# PCB_12V5A_60Wascii.net
KiCad netlist of a schematic drawn in Altium Designer
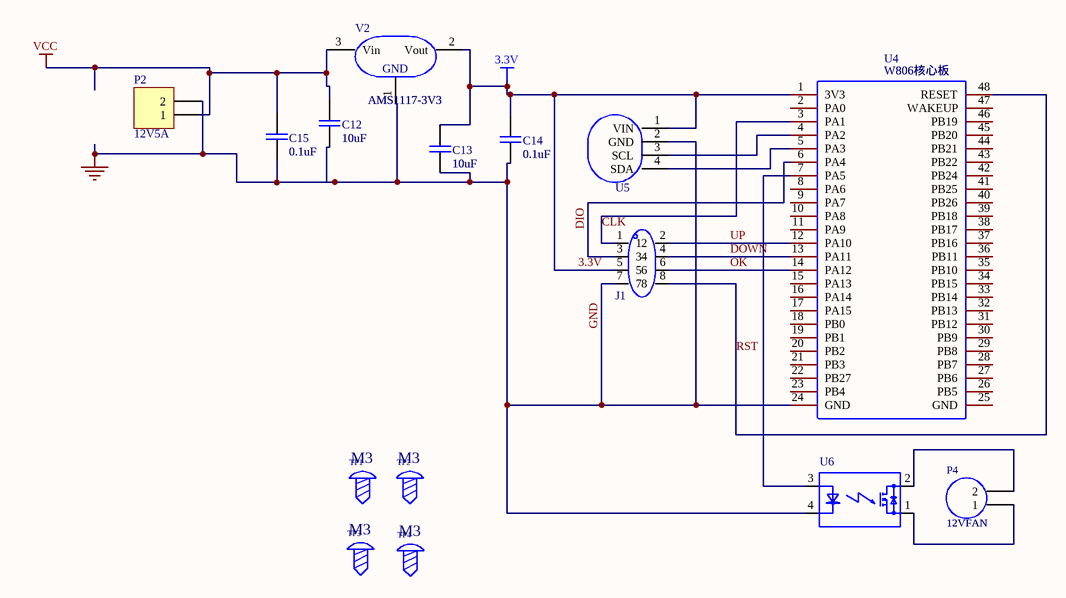
[diagram p0: PCB方案验证板  12V5A 60Wascii.SchDoc]

(export (version "E")
  (design (tool "Eeschema 10.0.6"))
  (components
    (comp (ref "C12")
      (value "10uF")
      (footprint "0805-C")
      (fields (field (name "NAME") "10uF"))
      (libsource (lib "altium-import") (part "root_1_CAP-SMT_"))
    )
    (comp (ref "C13")
      (value "10uF")
      (footprint "0805-C")
      (fields (field (name "NAME") "10uF"))
      (libsource (lib "altium-import") (part "root_1_CAP-SMT_"))
    )
    (comp (ref "C14")
      (value "0.1uF")
      (footprint "0805-C")
      (fields (field (name "NAME") "0.1uF"))
      (libsource (lib "altium-import") (part "root_1_CAP-SMT_"))
    )
    (comp (ref "C15")
      (value "0.1uF")
      (footprint "0805-C")
      (fields (field (name "NAME") "0.1uF"))
      (libsource (lib "") (part "root_1_CAP-SMT__1"))
    )
    (comp (ref "J1")
      (value "~")
      (footprint "HDR-TH_8P-P2.54-V-F-R2-C4-S2.54-1")
      (fields (field (name "MANUFACTURER PART") "2.54mm,24Doublerowfemale"))
      (libsource (lib "altium-import") (part "root_0_2.54mm,2×4Doublerowfemale_"))
    )
    (comp (ref "P2")
      (value "12V5A")
      (footprint "OUT")
      (description "Header, 2-Pin")
      (fields (field (name "PUBLISHER") "Altium Limited"))
      (libsource (lib "Miscellaneous Connectors") (part "Header 2"))
    )
    (comp (ref "P4")
      (value "12VFAN")
      (footprint "OUT")
      (fields (field (name "NAME") "12VFAN") (field (name "PUBLISHER") "Altium Limited"))
      (libsource (lib "altium-import") (part "root_2_12V5A_"))
    )
    (comp (ref "TP1")
      (value "~")
      (footprint "M3x8+6_N")
      (libsource (lib "altium-import") (part "root_0_M3_"))
    )
    (comp (ref "TP2")
      (value "~")
      (footprint "M3x8+6_N")
      (libsource (lib "altium-import") (part "root_0_M3_"))
    )
    (comp (ref "TP3")
      (value "~")
      (footprint "M3x8+6_N")
      (libsource (lib "altium-import") (part "root_0_M3_"))
    )
    (comp (ref "TP4")
      (value "~")
      (footprint "M3x8+6_N")
      (libsource (lib "altium-import") (part "root_0_M3_"))
    )
    (comp (ref "U4")
      (value "W806核心板")
      (footprint "w806")
      (fields (field (name "NAME") "W806核心板"))
      (libsource (lib "altium-import") (part "root_0_W806核心板_"))
    )
    (comp (ref "U5")
      (value "~")
      (footprint "AHT10")
      (libsource (lib "altium-import") (part "root_0_AHT10温湿度传感器_"))
    )
    (comp (ref "U6")
      (value "~")
      (footprint "w806:RELAY-TH_4P-L43.5-W10.3-PMN")
      (fields (field (name "MANUFACTURER") "PANASONIC(松下)") (field (name "MANUFACTURER PART") "AQZ102D"))
      (libsource (lib "altium-import") (part "root_0_PMN5D6132_ENMG_"))
    )
    (comp (ref "V2")
      (value "AMS1117-3V3")
      (footprint "PG-SOT223-4_L6.5-W3.5-P2.30-LS7.0-BR")
      (fields (field (name "NAME") "AMS1117-3V3"))
      (libsource (lib "altium-import") (part "root_0_AMS1117_"))
    )
  )
  (nets
    (net (code "1") (name "/CLK") (class "Default")
      (node (ref "J1") (pin "1") (pinfunction "1_1") (pintype "passive"))
      (node (ref "U4") (pin "3") (pinfunction "PA1_3") (pintype "passive"))
    )
    (net (code "2") (name "/DIO") (class "Default")
      (node (ref "J1") (pin "3") (pinfunction "3_3") (pintype "passive"))
      (node (ref "U4") (pin "6") (pinfunction "PA4_6") (pintype "passive"))
    )
    (net (code "3") (name "/DOWN") (class "Default")
      (node (ref "J1") (pin "4") (pinfunction "4_4") (pintype "passive"))
      (node (ref "U4") (pin "13") (pinfunction "PA11_13") (pintype "passive"))
    )
    (net (code "4") (name "/OK") (class "Default")
      (node (ref "J1") (pin "6") (pinfunction "6_6") (pintype "passive"))
      (node (ref "U4") (pin "14") (pinfunction "PA12_14") (pintype "passive"))
    )
    (net (code "5") (name "/RST") (class "Default")
      (node (ref "J1") (pin "8") (pinfunction "8_8") (pintype "passive"))
      (node (ref "U4") (pin "48") (pinfunction "RESET_48") (pintype "passive"))
    )
    (net (code "6") (name "/UP") (class "Default")
      (node (ref "J1") (pin "2") (pinfunction "2_2") (pintype "passive"))
      (node (ref "U4") (pin "12") (pinfunction "PA10_12") (pintype "passive"))
    )
    (net (code "7") (name "3.3V") (class "Default")
      (node (ref "C13") (pin "2") (pinfunction "2_2") (pintype "passive"))
      (node (ref "C14") (pin "2") (pinfunction "2_2") (pintype "passive"))
      (node (ref "J1") (pin "5") (pinfunction "5_5") (pintype "passive"))
      (node (ref "U4") (pin "1") (pinfunction "3V3_1") (pintype "passive"))
      (node (ref "U5") (pin "1") (pinfunction "VIN_1") (pintype "passive"))
      (node (ref "V2") (pin "2") (pinfunction "Vout_2") (pintype "passive"))
    )
    (net (code "8") (name "GND") (class "Default")
      (node (ref "C12") (pin "1") (pinfunction "1_1") (pintype "passive"))
      (node (ref "C13") (pin "1") (pinfunction "1_1") (pintype "passive"))
      (node (ref "C14") (pin "1") (pinfunction "1_1") (pintype "passive"))
      (node (ref "C15") (pin "1") (pinfunction "1_1") (pintype "passive"))
      (node (ref "J1") (pin "7") (pinfunction "7_7") (pintype "passive"))
      (node (ref "P2") (pin "GND") (pinfunction "2_GND") (pintype "passive"))
      (node (ref "U4") (pin "24") (pinfunction "GND_24") (pintype "passive"))
      (node (ref "U5") (pin "2") (pinfunction "GND_2") (pintype "passive"))
      (node (ref "U6") (pin "4") (pinfunction "+_4") (pintype "passive"))
      (node (ref "V2") (pin "1") (pinfunction "GND_1") (pintype "passive"))
    )
    (net (code "9") (name "Net-(P4-1)") (class "Default")
      (node (ref "P4") (pin "VCC") (pinfunction "1_VCC") (pintype "passive"))
      (node (ref "U6") (pin "1") (pinfunction "K_1") (pintype "passive"))
    )
    (net (code "10") (name "Net-(P4-2)") (class "Default")
      (node (ref "P4") (pin "GND") (pinfunction "2_GND") (pintype "passive"))
      (node (ref "U6") (pin "2") (pinfunction "A_2") (pintype "passive"))
    )
    (net (code "11") (name "Net-(U4-PA2)") (class "Default")
      (node (ref "U4") (pin "4") (pinfunction "PA2_4") (pintype "passive"))
      (node (ref "U5") (pin "3") (pinfunction "SCL_3") (pintype "passive"))
    )
    (net (code "12") (name "Net-(U4-PA3)") (class "Default")
      (node (ref "U4") (pin "5") (pinfunction "PA3_5") (pintype "passive"))
      (node (ref "U5") (pin "4") (pinfunction "SDA_4") (pintype "passive"))
    )
    (net (code "13") (name "Net-(U4-PA5)") (class "Default")
      (node (ref "U4") (pin "7") (pinfunction "PA5_7") (pintype "passive"))
      (node (ref "U6") (pin "3") (pinfunction "-_3") (pintype "passive"))
    )
    (net (code "14") (name "VCC") (class "Default")
      (node (ref "C12") (pin "2") (pinfunction "2_2") (pintype "passive"))
      (node (ref "C15") (pin "2") (pinfunction "2_2") (pintype "passive"))
      (node (ref "P2") (pin "VCC") (pinfunction "1_VCC") (pintype "passive"))
      (node (ref "V2") (pin "3") (pinfunction "Vin_3") (pintype "passive"))
    )
    (net (code "15") (name "unconnected-(U4-GND-Pad25)") (class "Default")
      (node (ref "U4") (pin "25") (pinfunction "GND_25") (pintype "passive"))
    )
    (net (code "16") (name "unconnected-(U4-PA0-Pad2)") (class "Default")
      (node (ref "U4") (pin "2") (pinfunction "PA0_2") (pintype "passive"))
    )
    (net (code "17") (name "unconnected-(U4-PA6-Pad8)") (class "Default")
      (node (ref "U4") (pin "8") (pinfunction "PA6_8") (pintype "passive"))
    )
    (net (code "18") (name "unconnected-(U4-PA7-Pad9)") (class "Default")
      (node (ref "U4") (pin "9") (pinfunction "PA7_9") (pintype "passive"))
    )
    (net (code "19") (name "unconnected-(U4-PA8-Pad10)") (class "Default")
      (node (ref "U4") (pin "10") (pinfunction "PA8_10") (pintype "passive"))
    )
    (net (code "20") (name "unconnected-(U4-PA9-Pad11)") (class "Default")
      (node (ref "U4") (pin "11") (pinfunction "PA9_11") (pintype "passive"))
    )
    (net (code "21") (name "unconnected-(U4-PA13-Pad15)") (class "Default")
      (node (ref "U4") (pin "15") (pinfunction "PA13_15") (pintype "passive"))
    )
    (net (code "22") (name "unconnected-(U4-PA14-Pad16)") (class "Default")
      (node (ref "U4") (pin "16") (pinfunction "PA14_16") (pintype "passive"))
    )
    (net (code "23") (name "unconnected-(U4-PA15-Pad17)") (class "Default")
      (node (ref "U4") (pin "17") (pinfunction "PA15_17") (pintype "passive"))
    )
    (net (code "24") (name "unconnected-(U4-PB0-Pad18)") (class "Default")
      (node (ref "U4") (pin "18") (pinfunction "PB0_18") (pintype "passive"))
    )
    (net (code "25") (name "unconnected-(U4-PB1-Pad19)") (class "Default")
      (node (ref "U4") (pin "19") (pinfunction "PB1_19") (pintype "passive"))
    )
    (net (code "26") (name "unconnected-(U4-PB2-Pad20)") (class "Default")
      (node (ref "U4") (pin "20") (pinfunction "PB2_20") (pintype "passive"))
    )
    (net (code "27") (name "unconnected-(U4-PB3-Pad21)") (class "Default")
      (node (ref "U4") (pin "21") (pinfunction "PB3_21") (pintype "passive"))
    )
    (net (code "28") (name "unconnected-(U4-PB4-Pad23)") (class "Default")
      (node (ref "U4") (pin "23") (pinfunction "PB4_23") (pintype "passive"))
    )
    (net (code "29") (name "unconnected-(U4-PB5-Pad26)") (class "Default")
      (node (ref "U4") (pin "26") (pinfunction "PB5_26") (pintype "passive"))
    )
    (net (code "30") (name "unconnected-(U4-PB6-Pad27)") (class "Default")
      (node (ref "U4") (pin "27") (pinfunction "PB6_27") (pintype "passive"))
    )
    (net (code "31") (name "unconnected-(U4-PB7-Pad28)") (class "Default")
      (node (ref "U4") (pin "28") (pinfunction "PB7_28") (pintype "passive"))
    )
    (net (code "32") (name "unconnected-(U4-PB8-Pad29)") (class "Default")
      (node (ref "U4") (pin "29") (pinfunction "PB8_29") (pintype "passive"))
    )
    (net (code "33") (name "unconnected-(U4-PB9-Pad30)") (class "Default")
      (node (ref "U4") (pin "30") (pinfunction "PB9_30") (pintype "passive"))
    )
    (net (code "34") (name "unconnected-(U4-PB10-Pad35)") (class "Default")
      (node (ref "U4") (pin "35") (pinfunction "PB10_35") (pintype "passive"))
    )
    (net (code "35") (name "unconnected-(U4-PB11-Pad36)") (class "Default")
      (node (ref "U4") (pin "36") (pinfunction "PB11_36") (pintype "passive"))
    )
    (net (code "36") (name "unconnected-(U4-PB12-Pad31)") (class "Default")
      (node (ref "U4") (pin "31") (pinfunction "PB12_31") (pintype "passive"))
    )
    (net (code "37") (name "unconnected-(U4-PB13-Pad32)") (class "Default")
      (node (ref "U4") (pin "32") (pinfunction "PB13_32") (pintype "passive"))
    )
    (net (code "38") (name "unconnected-(U4-PB14-Pad33)") (class "Default")
      (node (ref "U4") (pin "33") (pinfunction "PB14_33") (pintype "passive"))
    )
    (net (code "39") (name "unconnected-(U4-PB15-Pad34)") (class "Default")
      (node (ref "U4") (pin "34") (pinfunction "PB15_34") (pintype "passive"))
    )
    (net (code "40") (name "unconnected-(U4-PB16-Pad37)") (class "Default")
      (node (ref "U4") (pin "37") (pinfunction "PB16_37") (pintype "passive"))
    )
    (net (code "41") (name "unconnected-(U4-PB17-Pad38)") (class "Default")
      (node (ref "U4") (pin "38") (pinfunction "PB17_38") (pintype "passive"))
    )
    (net (code "42") (name "unconnected-(U4-PB18-Pad39)") (class "Default")
      (node (ref "U4") (pin "39") (pinfunction "PB18_39") (pintype "passive"))
    )
    (net (code "43") (name "unconnected-(U4-PB19-Pad46)") (class "Default")
      (node (ref "U4") (pin "46") (pinfunction "PB19_46") (pintype "passive"))
    )
    (net (code "44") (name "unconnected-(U4-PB20-Pad45)") (class "Default")
      (node (ref "U4") (pin "45") (pinfunction "PB20_45") (pintype "passive"))
    )
    (net (code "45") (name "unconnected-(U4-PB21-Pad44)") (class "Default")
      (node (ref "U4") (pin "44") (pinfunction "PB21_44") (pintype "passive"))
    )
    (net (code "46") (name "unconnected-(U4-PB22-Pad43)") (class "Default")
      (node (ref "U4") (pin "43") (pinfunction "PB22_43") (pintype "passive"))
    )
    (net (code "47") (name "unconnected-(U4-PB24-Pad42)") (class "Default")
      (node (ref "U4") (pin "42") (pinfunction "PB24_42") (pintype "passive"))
    )
    (net (code "48") (name "unconnected-(U4-PB25-Pad41)") (class "Default")
      (node (ref "U4") (pin "41") (pinfunction "PB25_41") (pintype "passive"))
    )
    (net (code "49") (name "unconnected-(U4-PB26-Pad40)") (class "Default")
      (node (ref "U4") (pin "40") (pinfunction "PB26_40") (pintype "passive"))
    )
    (net (code "50") (name "unconnected-(U4-PB27-Pad22)") (class "Default")
      (node (ref "U4") (pin "22") (pinfunction "PB27_22") (pintype "passive"))
    )
    (net (code "51") (name "unconnected-(U4-WAKEUP-Pad47)") (class "Default")
      (node (ref "U4") (pin "47") (pinfunction "WAKEUP_47") (pintype "passive"))
    )
  )
)
